# untitled.net
KiCad netlist of a schematic drawn in EAGLE
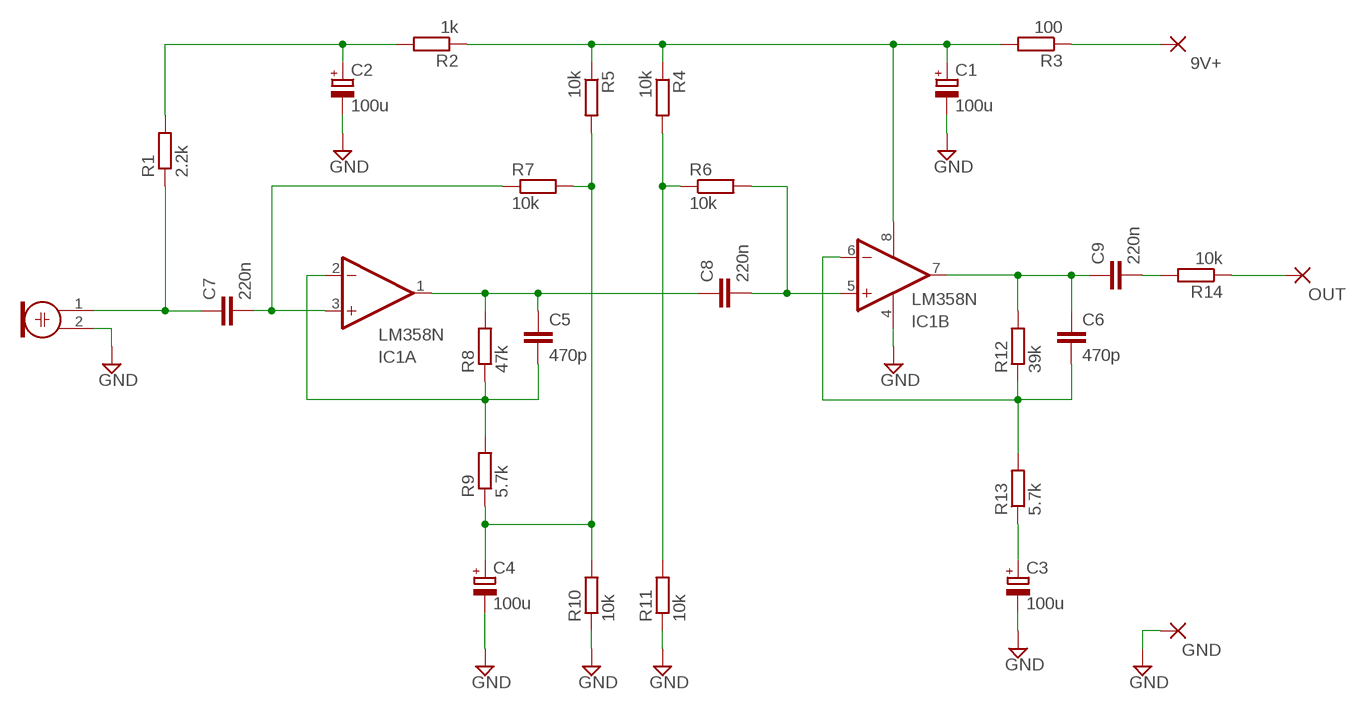
[diagram p0: schematic, sheet 1]

(export (version "E")
  (design (tool "Eeschema 10.0.6"))
  (components
    (comp (ref "9V+")
      (value "3,81/1,4")
      (footprint "eagle-import:3,81_1,4")
      (libsource (lib "eagle-import") (part "3,81/1,4"))
    )
    (comp (ref "C1")
      (value "100u")
      (footprint "eagle-import:E2-5")
      (libsource (lib "eagle-import") (part "CPOL-EUE2-5"))
    )
    (comp (ref "C2")
      (value "100u")
      (footprint "eagle-import:E2-5")
      (libsource (lib "eagle-import") (part "CPOL-EUE2-5"))
    )
    (comp (ref "C3")
      (value "100u")
      (footprint "eagle-import:E2-5")
      (libsource (lib "eagle-import") (part "CPOL-EUE2-5"))
    )
    (comp (ref "C4")
      (value "100u")
      (footprint "eagle-import:E2-5")
      (libsource (lib "eagle-import") (part "CPOL-EUE2-5"))
    )
    (comp (ref "C5")
      (value "470p")
      (footprint "eagle-import:C025-025X050")
      (libsource (lib "eagle-import") (part "C-EU025-025X050"))
    )
    (comp (ref "C6")
      (value "470p")
      (footprint "eagle-import:C025-025X050")
      (libsource (lib "eagle-import") (part "C-EU025-025X050"))
    )
    (comp (ref "C7")
      (value "220n")
      (footprint "eagle-import:C050-025X075")
      (libsource (lib "eagle-import") (part "C-EU050-025X075"))
    )
    (comp (ref "C8")
      (value "220n")
      (footprint "eagle-import:C050-025X075")
      (libsource (lib "eagle-import") (part "C-EU050-025X075"))
    )
    (comp (ref "C9")
      (value "220n")
      (footprint "eagle-import:C050-025X075")
      (libsource (lib "eagle-import") (part "C-EU050-025X075"))
    )
    (comp (ref "GND")
      (value "3,81/1,4")
      (footprint "eagle-import:3,81_1,4")
      (libsource (lib "eagle-import") (part "3,81/1,4"))
    )
    (comp (ref "IC1")
      (value "LM358N")
      (footprint "eagle-import:DIL08")
      (libsource (lib "eagle-import") (part "LM358N"))
    )
    (comp (ref "M1")
      (value "ELECTRET_MICROPHON-F6050AP")
      (footprint "eagle-import:F6050AP")
      (libsource (lib "eagle-import") (part "ELECTRET_MICROPHON-F6050AP"))
    )
    (comp (ref "OUT")
      (value "3,81/1,4")
      (footprint "eagle-import:3,81_1,4")
      (libsource (lib "eagle-import") (part "3,81/1,4"))
    )
    (comp (ref "R1")
      (value "2.2k")
      (footprint "eagle-import:0207_10")
      (libsource (lib "eagle-import") (part "R-EU_0207/10"))
    )
    (comp (ref "R2")
      (value "1k")
      (footprint "eagle-import:0207_10")
      (libsource (lib "eagle-import") (part "R-EU_0207/10"))
    )
    (comp (ref "R3")
      (value "100")
      (footprint "eagle-import:0207_10")
      (libsource (lib "eagle-import") (part "R-EU_0207/10"))
    )
    (comp (ref "R4")
      (value "10k")
      (footprint "eagle-import:0207_10")
      (libsource (lib "eagle-import") (part "R-EU_0207/10"))
    )
    (comp (ref "R5")
      (value "10k")
      (footprint "eagle-import:0207_10")
      (libsource (lib "eagle-import") (part "R-EU_0207/10"))
    )
    (comp (ref "R6")
      (value "10k")
      (footprint "eagle-import:0207_10")
      (libsource (lib "eagle-import") (part "R-EU_0207/10"))
    )
    (comp (ref "R7")
      (value "10k")
      (footprint "eagle-import:0207_10")
      (libsource (lib "eagle-import") (part "R-EU_0207/10"))
    )
    (comp (ref "R8")
      (value "47k")
      (footprint "eagle-import:0207_10")
      (libsource (lib "eagle-import") (part "R-EU_0207/10"))
    )
    (comp (ref "R9")
      (value "5.7k")
      (footprint "eagle-import:0207_10")
      (libsource (lib "eagle-import") (part "R-EU_0207/10"))
    )
    (comp (ref "R10")
      (value "10k")
      (footprint "eagle-import:0207_10")
      (libsource (lib "eagle-import") (part "R-EU_0207/10"))
    )
    (comp (ref "R11")
      (value "10k")
      (footprint "eagle-import:0207_10")
      (libsource (lib "eagle-import") (part "R-EU_0207/10"))
    )
    (comp (ref "R12")
      (value "39k")
      (footprint "eagle-import:0207_10")
      (libsource (lib "eagle-import") (part "R-EU_0207/10"))
    )
    (comp (ref "R13")
      (value "5.7k")
      (footprint "eagle-import:0207_10")
      (libsource (lib "eagle-import") (part "R-EU_0207/10"))
    )
    (comp (ref "R14")
      (value "10k")
      (footprint "eagle-import:0207_10")
      (libsource (lib "eagle-import") (part "R-EU_0207/10"))
    )
  )
  (nets
    (net (code "1") (name "GND") (class "Default")
      (node (ref "C1") (pin "-") (pinfunction "-_-") (pintype "passive"))
      (node (ref "C2") (pin "-") (pinfunction "-_-") (pintype "passive"))
      (node (ref "C3") (pin "-") (pinfunction "-_-") (pintype "passive"))
      (node (ref "C4") (pin "-") (pinfunction "-_-") (pintype "passive"))
      (node (ref "GND") (pin "1") (pinfunction "P_1") (pintype "passive"))
      (node (ref "IC1") (pin "4") (pinfunction "V-_4") (pintype "power_in"))
      (node (ref "M1") (pin "2") (pinfunction "2_2") (pintype "passive"))
      (node (ref "R10") (pin "1") (pinfunction "1_1") (pintype "passive"))
      (node (ref "R11") (pin "1") (pinfunction "1_1") (pintype "passive"))
    )
    (net (code "2") (name "Net-(9V+-P)") (class "Default")
      (node (ref "9V+") (pin "1") (pinfunction "P_1") (pintype "passive"))
      (node (ref "R3") (pin "1") (pinfunction "1_1") (pintype "passive"))
    )
    (net (code "3") (name "Net-(C2-Pad+)") (class "Default")
      (node (ref "C2") (pin "+") (pinfunction "+_+") (pintype "passive"))
      (node (ref "R1") (pin "2") (pinfunction "2_2") (pintype "passive"))
      (node (ref "R2") (pin "2") (pinfunction "2_2") (pintype "passive"))
    )
    (net (code "4") (name "Net-(C3-Pad+)") (class "Default")
      (node (ref "C3") (pin "+") (pinfunction "+_+") (pintype "passive"))
      (node (ref "R13") (pin "1") (pinfunction "1_1") (pintype "passive"))
    )
    (net (code "5") (name "Net-(C4-Pad+)") (class "Default")
      (node (ref "C4") (pin "+") (pinfunction "+_+") (pintype "passive"))
      (node (ref "R10") (pin "2") (pinfunction "2_2") (pintype "passive"))
      (node (ref "R5") (pin "2") (pinfunction "2_2") (pintype "passive"))
      (node (ref "R7") (pin "2") (pinfunction "2_2") (pintype "passive"))
      (node (ref "R9") (pin "1") (pinfunction "1_1") (pintype "passive"))
    )
    (net (code "6") (name "Net-(C7-Pad1)") (class "Default")
      (node (ref "C7") (pin "1") (pinfunction "1_1") (pintype "passive"))
      (node (ref "M1") (pin "1") (pinfunction "1_1") (pintype "passive"))
      (node (ref "R1") (pin "1") (pinfunction "1_1") (pintype "passive"))
    )
    (net (code "7") (name "Net-(C9-Pad2)") (class "Default")
      (node (ref "C9") (pin "2") (pinfunction "2_2") (pintype "passive"))
      (node (ref "R14") (pin "2") (pinfunction "2_2") (pintype "passive"))
    )
    (net (code "8") (name "Net-(IC1A-+IN)") (class "Default")
      (node (ref "C7") (pin "2") (pinfunction "2_2") (pintype "passive"))
      (node (ref "IC1") (pin "3") (pinfunction "+IN_3") (pintype "input"))
      (node (ref "R7") (pin "1") (pinfunction "1_1") (pintype "passive"))
    )
    (net (code "9") (name "Net-(IC1A--IN)") (class "Default")
      (node (ref "C5") (pin "2") (pinfunction "2_2") (pintype "passive"))
      (node (ref "IC1") (pin "2") (pinfunction "-IN_2") (pintype "input"))
      (node (ref "R8") (pin "1") (pinfunction "1_1") (pintype "passive"))
      (node (ref "R9") (pin "2") (pinfunction "2_2") (pintype "passive"))
    )
    (net (code "10") (name "Net-(IC1A-OUT)") (class "Default")
      (node (ref "C5") (pin "1") (pinfunction "1_1") (pintype "passive"))
      (node (ref "C8") (pin "1") (pinfunction "1_1") (pintype "passive"))
      (node (ref "IC1") (pin "1") (pinfunction "OUT_1") (pintype "output"))
      (node (ref "R8") (pin "2") (pinfunction "2_2") (pintype "passive"))
    )
    (net (code "11") (name "Net-(IC1B-+IN)") (class "Default")
      (node (ref "C8") (pin "2") (pinfunction "2_2") (pintype "passive"))
      (node (ref "IC1") (pin "5") (pinfunction "+IN_5") (pintype "input"))
      (node (ref "R6") (pin "2") (pinfunction "2_2") (pintype "passive"))
    )
    (net (code "12") (name "Net-(IC1B--IN)") (class "Default")
      (node (ref "C6") (pin "2") (pinfunction "2_2") (pintype "passive"))
      (node (ref "IC1") (pin "6") (pinfunction "-IN_6") (pintype "input"))
      (node (ref "R12") (pin "1") (pinfunction "1_1") (pintype "passive"))
      (node (ref "R13") (pin "2") (pinfunction "2_2") (pintype "passive"))
    )
    (net (code "13") (name "Net-(IC1B-OUT)") (class "Default")
      (node (ref "C6") (pin "1") (pinfunction "1_1") (pintype "passive"))
      (node (ref "C9") (pin "1") (pinfunction "1_1") (pintype "passive"))
      (node (ref "IC1") (pin "7") (pinfunction "OUT_7") (pintype "output"))
      (node (ref "R12") (pin "2") (pinfunction "2_2") (pintype "passive"))
    )
    (net (code "14") (name "Net-(IC1C-V+)") (class "Default")
      (node (ref "C1") (pin "+") (pinfunction "+_+") (pintype "passive"))
      (node (ref "IC1") (pin "8") (pinfunction "V+_8") (pintype "power_in"))
      (node (ref "R2") (pin "1") (pinfunction "1_1") (pintype "passive"))
      (node (ref "R3") (pin "2") (pinfunction "2_2") (pintype "passive"))
      (node (ref "R4") (pin "1") (pinfunction "1_1") (pintype "passive"))
      (node (ref "R5") (pin "1") (pinfunction "1_1") (pintype "passive"))
    )
    (net (code "15") (name "Net-(OUT-P)") (class "Default")
      (node (ref "OUT") (pin "1") (pinfunction "P_1") (pintype "passive"))
      (node (ref "R14") (pin "1") (pinfunction "1_1") (pintype "passive"))
    )
    (net (code "16") (name "Net-(R11-Pad2)") (class "Default")
      (node (ref "R11") (pin "2") (pinfunction "2_2") (pintype "passive"))
      (node (ref "R4") (pin "2") (pinfunction "2_2") (pintype "passive"))
      (node (ref "R6") (pin "1") (pinfunction "1_1") (pintype "passive"))
    )
  )
)
